# esp8266_GSM.net
KiCad netlist of a schematic drawn in EAGLE
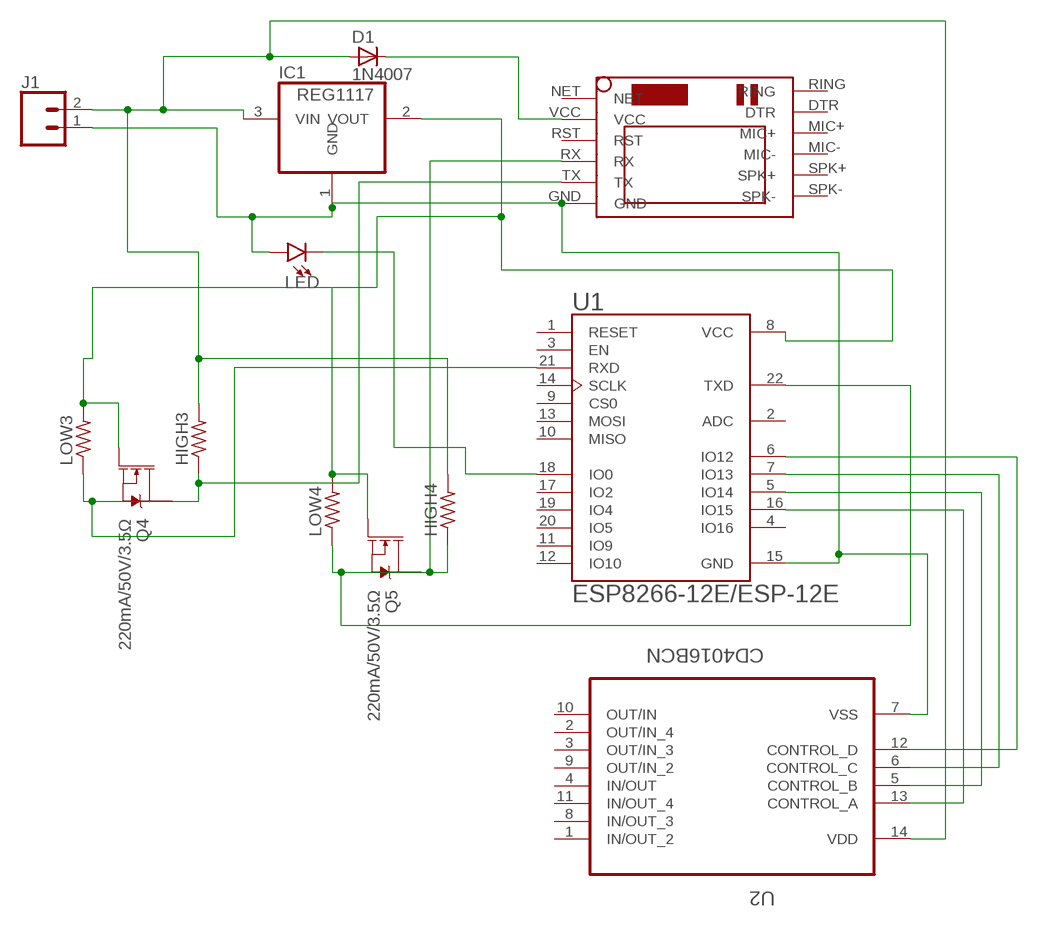
[diagram p0: schematic, sheet 1]
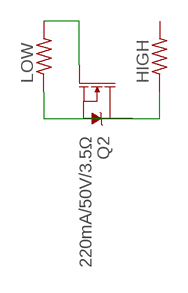
[diagram p1: schematic, sheet 2]

(export (version "E")
  (design (tool "Eeschema 10.0.6"))
  (components
    (comp (ref "D1")
      (value "1N4007")
      (footprint "eagle-import:SMA")
      (libsource (lib "eagle-import") (part "1N4007"))
    )
    (comp (ref "HIGH3")
      (value "R-US_R1206")
      (footprint "eagle-import:R1206")
      (libsource (lib "eagle-import") (part "R-US_R1206"))
    )
    (comp (ref "HIGH4")
      (value "R-US_R1206")
      (footprint "eagle-import:R1206")
      (libsource (lib "eagle-import") (part "R-US_R1206"))
    )
    (comp (ref "IC1")
      (value "REG1117")
      (footprint "eagle-import:SOT223")
      (libsource (lib "eagle-import") (part "REG1117"))
    )
    (comp (ref "J1")
      (value "CONN_025MM")
      (footprint "eagle-import:SCREWTERMINAL-5MM-2")
      (libsource (lib "eagle-import") (part "CONN_025MM"))
    )
    (comp (ref "LED")
      (value "LED1206")
      (footprint "eagle-import:LED-1206")
      (libsource (lib "eagle-import") (part "LED1206"))
    )
    (comp (ref "LOW3")
      (value "R-US_R1206")
      (footprint "eagle-import:R1206")
      (libsource (lib "eagle-import") (part "R-US_R1206"))
    )
    (comp (ref "LOW4")
      (value "R-US_R1206")
      (footprint "eagle-import:R1206")
      (libsource (lib "eagle-import") (part "R-US_R1206"))
    )
    (comp (ref "Q4")
      (value "220mA/50V/3.5Ω")
      (footprint "eagle-import:SOT23-3")
      (libsource (lib "eagle-import") (part "MOSFET-NCH-BSS138"))
    )
    (comp (ref "Q5")
      (value "220mA/50V/3.5Ω")
      (footprint "eagle-import:SOT23-3")
      (libsource (lib "eagle-import") (part "MOSFET-NCH-BSS138"))
    )
    (comp (ref "U$1")
      (value "SIM800LMODULE")
      (footprint "eagle-import:SIM800LMODULE")
      (libsource (lib "eagle-import") (part "SIM800LMODULE"))
    )
    (comp (ref "U1")
      (value "ESP8266-12E/ESP-12E")
      (footprint "eagle-import:XCVR_ESP8266-12E_ESP-12E")
      (fields (field (name "MF") "AI-Thinker"))
      (libsource (lib "eagle-import") (part "ESP8266-12E/ESP-12E"))
    )
    (comp (ref "U2")
      (value "CD4016BCN")
      (footprint "eagle-import:DIP254P762X508-14")
      (fields (field (name "MF") "ON Semiconductor"))
      (libsource (lib "eagle-import") (part "CD4016BCN"))
    )
    (comp (ref "HIGH")
      (value "R-US_R1206")
      (footprint "eagle-import:R1206")
      (libsource (lib "eagle-import") (part "R-US_R1206"))
    )
    (comp (ref "LOW")
      (value "R-US_R1206")
      (footprint "eagle-import:R1206")
      (libsource (lib "eagle-import") (part "R-US_R1206"))
    )
    (comp (ref "Q2")
      (value "220mA/50V/3.5Ω")
      (footprint "eagle-import:SOT23-3")
      (libsource (lib "eagle-import") (part "MOSFET-NCH-BSS138"))
    )
  )
  (nets
    (net (code "1") (name "Net-(D1-C)") (class "Default")
      (node (ref "D1") (pin "K") (pinfunction "C_K") (pintype "passive"))
      (node (ref "U$1") (pin "VCC") (pinfunction "VCC_VCC") (pintype "bidirectional"))
    )
    (net (code "2") (name "Net-(IC1-GND)") (class "Default")
      (node (ref "IC1") (pin "1") (pinfunction "GND_1") (pintype "power_in"))
      (node (ref "J1") (pin "1") (pinfunction "1_1") (pintype "passive"))
      (node (ref "LED") (pin "A") (pinfunction "A_A") (pintype "passive"))
      (node (ref "U$1") (pin "GND") (pinfunction "GND_GND") (pintype "bidirectional"))
      (node (ref "U1") (pin "15") (pinfunction "GND_15") (pintype "power_in"))
      (node (ref "U2") (pin "7") (pinfunction "VSS_7") (pintype "power_in"))
    )
    (net (code "3") (name "Net-(IC1-VIN)") (class "Default")
      (node (ref "D1") (pin "A") (pinfunction "A_A") (pintype "passive"))
      (node (ref "HIGH3") (pin "2") (pinfunction "2_2") (pintype "passive"))
      (node (ref "HIGH4") (pin "2") (pinfunction "2_2") (pintype "passive"))
      (node (ref "IC1") (pin "3") (pinfunction "VIN_3") (pintype "input"))
      (node (ref "J1") (pin "2") (pinfunction "2_2") (pintype "passive"))
      (node (ref "U2") (pin "14") (pinfunction "VDD_14") (pintype "power_in"))
    )
    (net (code "4") (name "Net-(IC1-VOUT)") (class "Default")
      (node (ref "IC1") (pin "2") (pinfunction "VOUT_2") (pintype "output"))
      (node (ref "LOW3") (pin "2") (pinfunction "2_2") (pintype "passive"))
      (node (ref "LOW4") (pin "2") (pinfunction "2_2") (pintype "passive"))
      (node (ref "Q4") (pin "1") (pinfunction "G_1") (pintype "bidirectional"))
      (node (ref "Q5") (pin "1") (pinfunction "G_1") (pintype "bidirectional"))
      (node (ref "U1") (pin "8") (pinfunction "VCC_8") (pintype "power_in"))
    )
    (net (code "5") (name "Net-(Q2-D)") (class "Default")
      (node (ref "LOW") (pin "1") (pinfunction "1_1") (pintype "passive"))
      (node (ref "Q2") (pin "3") (pinfunction "D_3") (pintype "bidirectional"))
    )
    (net (code "6") (name "Net-(Q2-G)") (class "Default")
      (node (ref "LOW") (pin "2") (pinfunction "2_2") (pintype "passive"))
      (node (ref "Q2") (pin "1") (pinfunction "G_1") (pintype "bidirectional"))
    )
    (net (code "7") (name "Net-(Q2-S)") (class "Default")
      (node (ref "HIGH") (pin "1") (pinfunction "1_1") (pintype "passive"))
      (node (ref "Q2") (pin "2") (pinfunction "S_2") (pintype "bidirectional"))
    )
    (net (code "8") (name "Net-(Q4-D)") (class "Default")
      (node (ref "LOW3") (pin "1") (pinfunction "1_1") (pintype "passive"))
      (node (ref "Q4") (pin "3") (pinfunction "D_3") (pintype "bidirectional"))
      (node (ref "U1") (pin "21") (pinfunction "RXD_21") (pintype "input"))
    )
    (net (code "9") (name "Net-(Q4-S)") (class "Default")
      (node (ref "HIGH3") (pin "1") (pinfunction "1_1") (pintype "passive"))
      (node (ref "Q4") (pin "2") (pinfunction "S_2") (pintype "bidirectional"))
      (node (ref "U$1") (pin "TX") (pinfunction "TX_TX") (pintype "bidirectional"))
    )
    (net (code "10") (name "Net-(Q5-D)") (class "Default")
      (node (ref "LOW4") (pin "1") (pinfunction "1_1") (pintype "passive"))
      (node (ref "Q5") (pin "3") (pinfunction "D_3") (pintype "bidirectional"))
      (node (ref "U1") (pin "22") (pinfunction "TXD_22") (pintype "output"))
    )
    (net (code "11") (name "Net-(Q5-S)") (class "Default")
      (node (ref "HIGH4") (pin "1") (pinfunction "1_1") (pintype "passive"))
      (node (ref "Q5") (pin "2") (pinfunction "S_2") (pintype "bidirectional"))
      (node (ref "U$1") (pin "RX") (pinfunction "RX_RX") (pintype "bidirectional"))
    )
    (net (code "12") (name "Net-(U1-IO0)") (class "Default")
      (node (ref "LED") (pin "C") (pinfunction "C_C") (pintype "passive"))
      (node (ref "U1") (pin "18") (pinfunction "IO0_18") (pintype "bidirectional"))
    )
    (net (code "13") (name "Net-(U1-IO12)") (class "Default")
      (node (ref "U1") (pin "6") (pinfunction "IO12_6") (pintype "bidirectional"))
      (node (ref "U2") (pin "12") (pinfunction "CONTROL_D_12") (pintype "input"))
    )
    (net (code "14") (name "Net-(U1-IO13)") (class "Default")
      (node (ref "U1") (pin "7") (pinfunction "IO13_7") (pintype "bidirectional"))
      (node (ref "U2") (pin "6") (pinfunction "CONTROL_C_6") (pintype "input"))
    )
    (net (code "15") (name "Net-(U1-IO14)") (class "Default")
      (node (ref "U1") (pin "5") (pinfunction "IO14_5") (pintype "bidirectional"))
      (node (ref "U2") (pin "5") (pinfunction "CONTROL_B_5") (pintype "input"))
    )
    (net (code "16") (name "Net-(U1-IO15)") (class "Default")
      (node (ref "U1") (pin "16") (pinfunction "IO15_16") (pintype "bidirectional"))
      (node (ref "U2") (pin "13") (pinfunction "CONTROL_A_13") (pintype "input"))
    )
    (net (code "17") (name "unconnected-(HIGH-Pad2)") (class "Default")
      (node (ref "HIGH") (pin "2") (pinfunction "2_2") (pintype "passive"))
    )
    (net (code "18") (name "unconnected-(U$1-PadDTR)") (class "Default")
      (node (ref "U$1") (pin "DTR") (pinfunction "DTR_DTR") (pintype "bidirectional"))
    )
    (net (code "19") (name "unconnected-(U$1-PadMIC+)") (class "Default")
      (node (ref "U$1") (pin "MIC+") (pinfunction "MIC+_MIC+") (pintype "bidirectional"))
    )
    (net (code "20") (name "unconnected-(U$1-PadMIC-)") (class "Default")
      (node (ref "U$1") (pin "MIC-") (pinfunction "MIC-_MIC-") (pintype "bidirectional"))
    )
    (net (code "21") (name "unconnected-(U$1-PadNET)") (class "Default")
      (node (ref "U$1") (pin "NET") (pinfunction "NET_NET") (pintype "bidirectional"))
    )
    (net (code "22") (name "unconnected-(U$1-PadRING)") (class "Default")
      (node (ref "U$1") (pin "RING") (pinfunction "RING_RING") (pintype "bidirectional"))
    )
    (net (code "23") (name "unconnected-(U$1-PadRST)") (class "Default")
      (node (ref "U$1") (pin "RST") (pinfunction "RST_RST") (pintype "bidirectional"))
    )
    (net (code "24") (name "unconnected-(U$1-PadSPK+)") (class "Default")
      (node (ref "U$1") (pin "SPK+") (pinfunction "SPK+_SPK+") (pintype "bidirectional"))
    )
    (net (code "25") (name "unconnected-(U$1-PadSPK-)") (class "Default")
      (node (ref "U$1") (pin "SPK-") (pinfunction "SPK-_SPK-") (pintype "bidirectional"))
    )
    (net (code "26") (name "unconnected-(U1-ADC-Pad2)") (class "Default")
      (node (ref "U1") (pin "2") (pinfunction "ADC_2") (pintype "passive"))
    )
    (net (code "27") (name "unconnected-(U1-CS0-Pad9)") (class "Default")
      (node (ref "U1") (pin "9") (pinfunction "CS0_9") (pintype "input"))
    )
    (net (code "28") (name "unconnected-(U1-EN-Pad3)") (class "Default")
      (node (ref "U1") (pin "3") (pinfunction "EN_3") (pintype "input"))
    )
    (net (code "29") (name "unconnected-(U1-IO2-Pad17)") (class "Default")
      (node (ref "U1") (pin "17") (pinfunction "IO2_17") (pintype "bidirectional"))
    )
    (net (code "30") (name "unconnected-(U1-IO4-Pad19)") (class "Default")
      (node (ref "U1") (pin "19") (pinfunction "IO4_19") (pintype "bidirectional"))
    )
    (net (code "31") (name "unconnected-(U1-IO5-Pad20)") (class "Default")
      (node (ref "U1") (pin "20") (pinfunction "IO5_20") (pintype "bidirectional"))
    )
    (net (code "32") (name "unconnected-(U1-IO9-Pad11)") (class "Default")
      (node (ref "U1") (pin "11") (pinfunction "IO9_11") (pintype "bidirectional"))
    )
    (net (code "33") (name "unconnected-(U1-IO10-Pad12)") (class "Default")
      (node (ref "U1") (pin "12") (pinfunction "IO10_12") (pintype "bidirectional"))
    )
    (net (code "34") (name "unconnected-(U1-IO16-Pad4)") (class "Default")
      (node (ref "U1") (pin "4") (pinfunction "IO16_4") (pintype "bidirectional"))
    )
    (net (code "35") (name "unconnected-(U1-MISO-Pad10)") (class "Default")
      (node (ref "U1") (pin "10") (pinfunction "MISO_10") (pintype "bidirectional"))
    )
    (net (code "36") (name "unconnected-(U1-MOSI-Pad13)") (class "Default")
      (node (ref "U1") (pin "13") (pinfunction "MOSI_13") (pintype "bidirectional"))
    )
    (net (code "37") (name "unconnected-(U1-RESET-Pad1)") (class "Default")
      (node (ref "U1") (pin "1") (pinfunction "RESET_1") (pintype "input"))
    )
    (net (code "38") (name "unconnected-(U1-SCLK-Pad14)") (class "Default")
      (node (ref "U1") (pin "14") (pinfunction "SCLK_14") (pintype "input"))
    )
    (net (code "39") (name "unconnected-(U2-IN{slash}OUT-Pad4)") (class "Default")
      (node (ref "U2") (pin "4") (pinfunction "IN/OUT_4") (pintype "bidirectional"))
    )
    (net (code "40") (name "unconnected-(U2-IN{slash}OUT_2-Pad1)") (class "Default")
      (node (ref "U2") (pin "1") (pinfunction "IN/OUT_2_1") (pintype "bidirectional"))
    )
    (net (code "41") (name "unconnected-(U2-IN{slash}OUT_3-Pad8)") (class "Default")
      (node (ref "U2") (pin "8") (pinfunction "IN/OUT_3_8") (pintype "bidirectional"))
    )
    (net (code "42") (name "unconnected-(U2-IN{slash}OUT_4-Pad11)") (class "Default")
      (node (ref "U2") (pin "11") (pinfunction "IN/OUT_4_11") (pintype "bidirectional"))
    )
    (net (code "43") (name "unconnected-(U2-OUT{slash}IN-Pad10)") (class "Default")
      (node (ref "U2") (pin "10") (pinfunction "OUT/IN_10") (pintype "bidirectional"))
    )
    (net (code "44") (name "unconnected-(U2-OUT{slash}IN_2-Pad9)") (class "Default")
      (node (ref "U2") (pin "9") (pinfunction "OUT/IN_2_9") (pintype "bidirectional"))
    )
    (net (code "45") (name "unconnected-(U2-OUT{slash}IN_3-Pad3)") (class "Default")
      (node (ref "U2") (pin "3") (pinfunction "OUT/IN_3_3") (pintype "bidirectional"))
    )
    (net (code "46") (name "unconnected-(U2-OUT{slash}IN_4-Pad2)") (class "Default")
      (node (ref "U2") (pin "2") (pinfunction "OUT/IN_4_2") (pintype "bidirectional"))
    )
  )
)
